# Arduino_Sheild.net
KiCad netlist of a schematic drawn in EAGLE
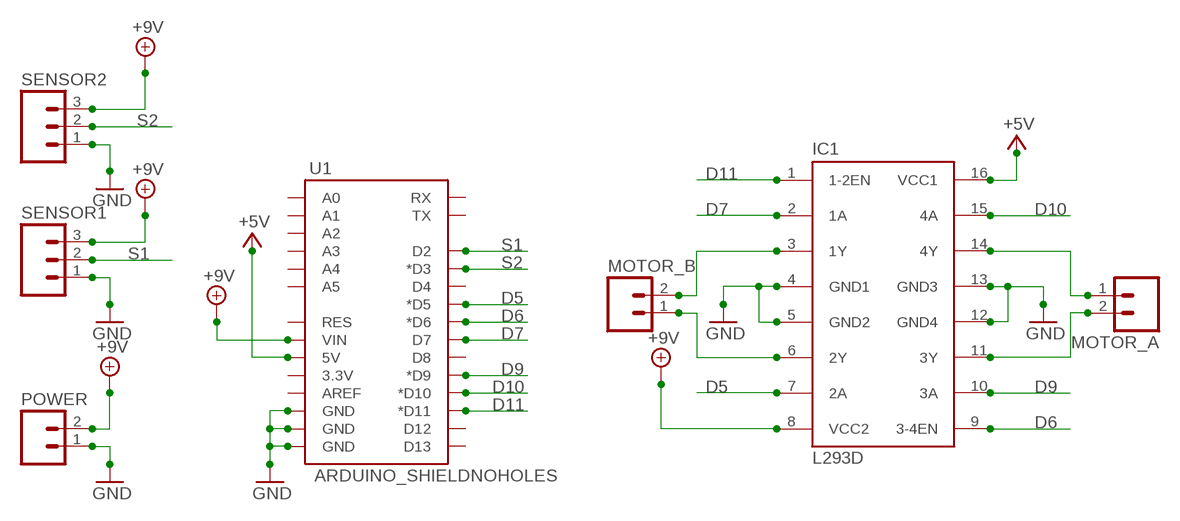
[diagram p0: schematic, sheet 1]

(export (version "E")
  (design (tool "Eeschema 10.0.6"))
  (components
    (comp (ref "IC1")
      (value "L293D")
      (footprint "eagle-import:DIL16")
      (libsource (lib "eagle-import") (part "L293D"))
    )
    (comp (ref "MOTOR_A")
      (value "M02")
      (footprint "eagle-import:02P")
      (libsource (lib "eagle-import") (part "M02"))
    )
    (comp (ref "MOTOR_B")
      (value "M02")
      (footprint "eagle-import:02P")
      (libsource (lib "eagle-import") (part "M02"))
    )
    (comp (ref "POWER")
      (value "M02")
      (footprint "eagle-import:02P")
      (libsource (lib "eagle-import") (part "M02"))
    )
    (comp (ref "SENSOR1")
      (value "M03")
      (footprint "eagle-import:03P")
      (libsource (lib "eagle-import") (part "M03"))
    )
    (comp (ref "SENSOR2")
      (value "M03")
      (footprint "eagle-import:03P")
      (libsource (lib "eagle-import") (part "M03"))
    )
    (comp (ref "U1")
      (value "ARDUINO_SHIELDNOHOLES")
      (footprint "eagle-import:DUEMILANOVE_SHIELD_NOHOLES")
      (libsource (lib "eagle-import") (part "ARDUINO_SHIELDNOHOLES"))
    )
  )
  (nets
    (net (code "1") (name "+5V") (class "Default")
      (node (ref "IC1") (pin "16") (pinfunction "VCC1_16") (pintype "power_in"))
      (node (ref "U1") (pin "5V") (pinfunction "5V_5V") (pintype "bidirectional"))
    )
    (net (code "2") (name "+9V") (class "Default")
      (node (ref "IC1") (pin "8") (pinfunction "VCC2_8") (pintype "power_in"))
      (node (ref "POWER") (pin "2") (pinfunction "2_2") (pintype "passive"))
      (node (ref "SENSOR1") (pin "3") (pinfunction "3_3") (pintype "passive"))
      (node (ref "SENSOR2") (pin "3") (pinfunction "3_3") (pintype "passive"))
      (node (ref "U1") (pin "VIN") (pinfunction "VIN_VIN") (pintype "bidirectional"))
    )
    (net (code "3") (name "/D5") (class "Default")
      (node (ref "IC1") (pin "7") (pinfunction "2A_7") (pintype "input"))
      (node (ref "U1") (pin "D5") (pinfunction "*D5_D5") (pintype "bidirectional"))
    )
    (net (code "4") (name "/D6") (class "Default")
      (node (ref "IC1") (pin "9") (pinfunction "3-4EN_9") (pintype "input"))
      (node (ref "U1") (pin "D6") (pinfunction "*D6_D6") (pintype "bidirectional"))
    )
    (net (code "5") (name "/D7") (class "Default")
      (node (ref "IC1") (pin "2") (pinfunction "1A_2") (pintype "input"))
      (node (ref "U1") (pin "D7") (pinfunction "D7_D7") (pintype "bidirectional"))
    )
    (net (code "6") (name "/D9") (class "Default")
      (node (ref "IC1") (pin "10") (pinfunction "3A_10") (pintype "input"))
      (node (ref "U1") (pin "D9") (pinfunction "*D9_D9") (pintype "bidirectional"))
    )
    (net (code "7") (name "/D10") (class "Default")
      (node (ref "IC1") (pin "15") (pinfunction "4A_15") (pintype "input"))
      (node (ref "U1") (pin "D10") (pinfunction "*D10_D10") (pintype "bidirectional"))
    )
    (net (code "8") (name "/D11") (class "Default")
      (node (ref "IC1") (pin "1") (pinfunction "1-2EN_1") (pintype "input"))
      (node (ref "U1") (pin "D11") (pinfunction "*D11_D11") (pintype "bidirectional"))
    )
    (net (code "9") (name "/S1") (class "Default")
      (node (ref "SENSOR1") (pin "2") (pinfunction "2_2") (pintype "passive"))
      (node (ref "U1") (pin "D2") (pinfunction "D2_D2") (pintype "bidirectional"))
    )
    (net (code "10") (name "/S2") (class "Default")
      (node (ref "SENSOR2") (pin "2") (pinfunction "2_2") (pintype "passive"))
      (node (ref "U1") (pin "D3") (pinfunction "*D3_D3") (pintype "bidirectional"))
    )
    (net (code "11") (name "GND") (class "Default")
      (node (ref "IC1") (pin "12") (pinfunction "GND4_12") (pintype "power_in"))
      (node (ref "IC1") (pin "13") (pinfunction "GND3_13") (pintype "power_in"))
      (node (ref "IC1") (pin "4") (pinfunction "GND1_4") (pintype "power_in"))
      (node (ref "IC1") (pin "5") (pinfunction "GND2_5") (pintype "power_in"))
      (node (ref "POWER") (pin "1") (pinfunction "1_1") (pintype "passive"))
      (node (ref "SENSOR1") (pin "1") (pinfunction "1_1") (pintype "passive"))
      (node (ref "SENSOR2") (pin "1") (pinfunction "1_1") (pintype "passive"))
      (node (ref "U1") (pin "GND@0") (pinfunction "GND_GND@0") (pintype "bidirectional"))
      (node (ref "U1") (pin "GND@1") (pinfunction "GND_GND@1") (pintype "bidirectional"))
      (node (ref "U1") (pin "GND@2") (pinfunction "GND_GND@2") (pintype "bidirectional"))
    )
    (net (code "12") (name "Net-(IC1-1Y)") (class "Default")
      (node (ref "IC1") (pin "3") (pinfunction "1Y_3") (pintype "output"))
      (node (ref "MOTOR_B") (pin "2") (pinfunction "2_2") (pintype "passive"))
    )
    (net (code "13") (name "Net-(IC1-2Y)") (class "Default")
      (node (ref "IC1") (pin "6") (pinfunction "2Y_6") (pintype "output"))
      (node (ref "MOTOR_B") (pin "1") (pinfunction "1_1") (pintype "passive"))
    )
    (net (code "14") (name "Net-(IC1-3Y)") (class "Default")
      (node (ref "IC1") (pin "11") (pinfunction "3Y_11") (pintype "output"))
      (node (ref "MOTOR_A") (pin "2") (pinfunction "2_2") (pintype "passive"))
    )
    (net (code "15") (name "Net-(IC1-4Y)") (class "Default")
      (node (ref "IC1") (pin "14") (pinfunction "4Y_14") (pintype "output"))
      (node (ref "MOTOR_A") (pin "1") (pinfunction "1_1") (pintype "passive"))
    )
    (net (code "16") (name "unconnected-(U1-Pad3.3V)") (class "Default")
      (node (ref "U1") (pin "3.3V") (pinfunction "3.3V_3.3V") (pintype "bidirectional"))
    )
    (net (code "17") (name "unconnected-(U1-PadA0)") (class "Default")
      (node (ref "U1") (pin "A0") (pinfunction "A0_A0") (pintype "bidirectional"))
    )
    (net (code "18") (name "unconnected-(U1-PadA1)") (class "Default")
      (node (ref "U1") (pin "A1") (pinfunction "A1_A1") (pintype "bidirectional"))
    )
    (net (code "19") (name "unconnected-(U1-PadA2)") (class "Default")
      (node (ref "U1") (pin "A2") (pinfunction "A2_A2") (pintype "bidirectional"))
    )
    (net (code "20") (name "unconnected-(U1-PadA3)") (class "Default")
      (node (ref "U1") (pin "A3") (pinfunction "A3_A3") (pintype "bidirectional"))
    )
    (net (code "21") (name "unconnected-(U1-PadA4)") (class "Default")
      (node (ref "U1") (pin "A4") (pinfunction "A4_A4") (pintype "bidirectional"))
    )
    (net (code "22") (name "unconnected-(U1-PadA5)") (class "Default")
      (node (ref "U1") (pin "A5") (pinfunction "A5_A5") (pintype "bidirectional"))
    )
    (net (code "23") (name "unconnected-(U1-PadAREF)") (class "Default")
      (node (ref "U1") (pin "AREF") (pinfunction "AREF_AREF") (pintype "bidirectional"))
    )
    (net (code "24") (name "unconnected-(U1-PadD4)") (class "Default")
      (node (ref "U1") (pin "D4") (pinfunction "D4_D4") (pintype "bidirectional"))
    )
    (net (code "25") (name "unconnected-(U1-PadD8)") (class "Default")
      (node (ref "U1") (pin "D8") (pinfunction "D8_D8") (pintype "bidirectional"))
    )
    (net (code "26") (name "unconnected-(U1-PadD12)") (class "Default")
      (node (ref "U1") (pin "D12") (pinfunction "D12_D12") (pintype "bidirectional"))
    )
    (net (code "27") (name "unconnected-(U1-PadD13)") (class "Default")
      (node (ref "U1") (pin "D13") (pinfunction "D13_D13") (pintype "bidirectional"))
    )
    (net (code "28") (name "unconnected-(U1-PadRES)") (class "Default")
      (node (ref "U1") (pin "RES") (pinfunction "RES_RES") (pintype "bidirectional"))
    )
    (net (code "29") (name "unconnected-(U1-PadRX)") (class "Default")
      (node (ref "U1") (pin "RX") (pinfunction "RX_RX") (pintype "bidirectional"))
    )
    (net (code "30") (name "unconnected-(U1-PadTX)") (class "Default")
      (node (ref "U1") (pin "TX") (pinfunction "TX_TX") (pintype "bidirectional"))
    )
  )
)
